# SoundChip.net
KiCad netlist of a schematic drawn in Altium Designer
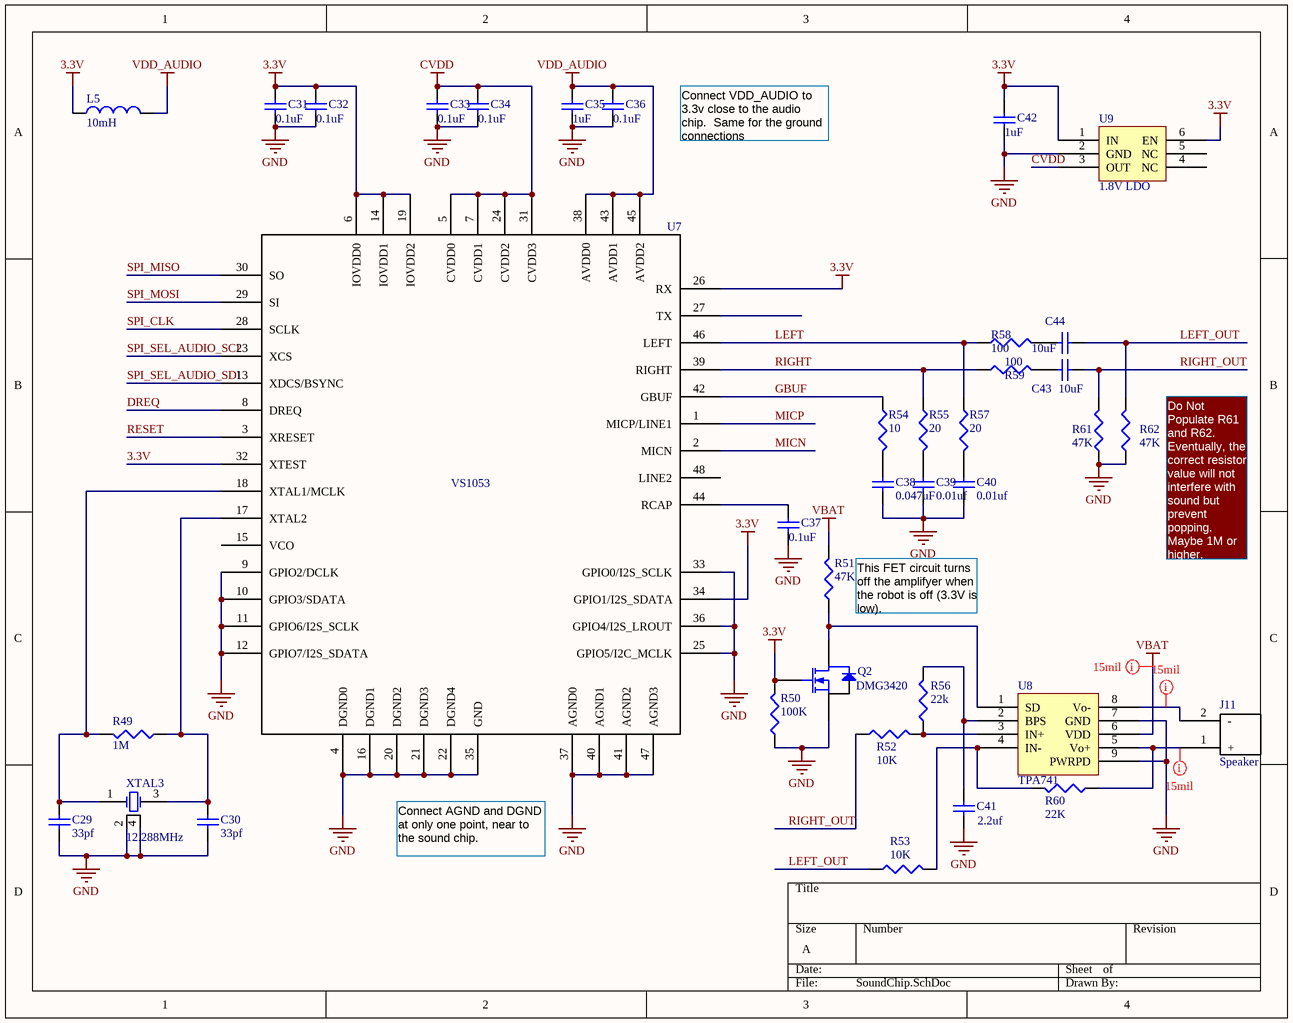
[diagram p0: SoundChip.SchDoc]

(export (version "E")
  (design (tool "Eeschema 10.0.6"))
  (components
    (comp (ref "C29")
      (value "33pf")
      (footprint "CAPC1005L")
      (description "Capacitor (Semiconductor SIM Model)")
      (fields (field (name "Comment") "Cap Semi") (field (name "PUBLISHER") "Altium Limited"))
      (libsource (lib "Miscellaneous Devices") (part "Cap Semi"))
    )
    (comp (ref "C30")
      (value "33pf")
      (footprint "CAPC1005L")
      (description "Capacitor (Semiconductor SIM Model)")
      (fields (field (name "Comment") "Cap Semi") (field (name "PUBLISHER") "Altium Limited"))
      (libsource (lib "Miscellaneous Devices") (part "Cap Semi"))
    )
    (comp (ref "C31")
      (value "0.1uF")
      (footprint "CAPC1005L")
      (description "Capacitor (Semiconductor SIM Model)")
      (fields (field (name "Comment") "Cap Semi") (field (name "PUBLISHER") "Altium Limited"))
      (libsource (lib "Miscellaneous Devices") (part "Cap Semi"))
    )
    (comp (ref "C32")
      (value "0.1uF")
      (footprint "CAPC1005L")
      (description "Capacitor (Semiconductor SIM Model)")
      (fields (field (name "Comment") "Cap Semi") (field (name "PUBLISHER") "Altium Limited"))
      (libsource (lib "Miscellaneous Devices") (part "Cap Semi"))
    )
    (comp (ref "C33")
      (value "0.1uF")
      (footprint "CAPC1005L")
      (description "Capacitor (Semiconductor SIM Model)")
      (fields (field (name "Comment") "Cap Semi") (field (name "PUBLISHER") "Altium Limited"))
      (libsource (lib "Miscellaneous Devices") (part "Cap Semi"))
    )
    (comp (ref "C34")
      (value "0.1uF")
      (footprint "CAPC1005L")
      (description "Capacitor (Semiconductor SIM Model)")
      (fields (field (name "Comment") "Cap Semi") (field (name "PUBLISHER") "Altium Limited"))
      (libsource (lib "Miscellaneous Devices") (part "Cap Semi"))
    )
    (comp (ref "C35")
      (value "1uF")
      (footprint "CAPC1608L")
      (description "Capacitor (Semiconductor SIM Model)")
      (fields (field (name "Comment") "Cap Semi") (field (name "PUBLISHER") "Altium Limited"))
      (libsource (lib "Miscellaneous Devices") (part "Cap Semi"))
    )
    (comp (ref "C36")
      (value "0.1uF")
      (footprint "CAPC1005L")
      (description "Capacitor (Semiconductor SIM Model)")
      (fields (field (name "Comment") "Cap Semi") (field (name "PUBLISHER") "Altium Limited"))
      (libsource (lib "Miscellaneous Devices") (part "Cap Semi"))
    )
    (comp (ref "C37")
      (value "0.1uF")
      (footprint "CAPC1005L")
      (description "Capacitor (Semiconductor SIM Model)")
      (fields (field (name "Comment") "Cap Semi") (field (name "PUBLISHER") "Altium Limited"))
      (libsource (lib "Miscellaneous Devices") (part "Cap Semi"))
    )
    (comp (ref "C38")
      (value "0.047uF")
      (footprint "CAPC1005L")
      (description "Capacitor (Semiconductor SIM Model)")
      (fields (field (name "Comment") "Cap Semi") (field (name "PUBLISHER") "Altium Limited"))
      (libsource (lib "Miscellaneous Devices") (part "Cap Semi"))
    )
    (comp (ref "C39")
      (value "0.01uf")
      (footprint "CAPC1005L")
      (description "Capacitor (Semiconductor SIM Model)")
      (fields (field (name "Comment") "Cap Semi") (field (name "PUBLISHER") "Altium Limited"))
      (libsource (lib "Miscellaneous Devices") (part "Cap Semi"))
    )
    (comp (ref "C40")
      (value "0.01uf")
      (footprint "CAPC1005L")
      (description "Capacitor (Semiconductor SIM Model)")
      (fields (field (name "Comment") "Cap Semi") (field (name "PUBLISHER") "Altium Limited"))
      (libsource (lib "Miscellaneous Devices") (part "Cap Semi"))
    )
    (comp (ref "C41")
      (value "2.2uf")
      (footprint "J1-0603")
      (description "Capacitor (Semiconductor SIM Model)")
      (fields (field (name "Comment") "Cap Semi") (field (name "PUBLISHER") "Altium Limited"))
      (libsource (lib "Miscellaneous Devices") (part "Cap Semi"))
    )
    (comp (ref "C42")
      (value "1uF")
      (footprint "CAPC1608L")
      (description "Capacitor (Semiconductor SIM Model)")
      (fields (field (name "Comment") "Cap Semi") (field (name "PUBLISHER") "Altium Limited"))
      (libsource (lib "Miscellaneous Devices") (part "Cap Semi"))
    )
    (comp (ref "C43")
      (value "10uF")
      (footprint "CAPC1608L")
      (description "Capacitor (Semiconductor SIM Model)")
      (fields (field (name "Comment") "Cap Semi") (field (name "PUBLISHER") "Altium Limited"))
      (libsource (lib "Miscellaneous Devices") (part "Cap Semi"))
    )
    (comp (ref "C44")
      (value "10uF")
      (footprint "CAPC1608L")
      (description "Capacitor (Semiconductor SIM Model)")
      (fields (field (name "Comment") "Cap Semi") (field (name "PUBLISHER") "Altium Limited"))
      (libsource (lib "Miscellaneous Devices") (part "Cap Semi"))
    )
    (comp (ref "J11")
      (value "Speaker")
      (footprint "BatteryConnJST")
      (libsource (lib "mrone") (part "BatteryConnJST"))
    )
    (comp (ref "L5")
      (value "10mH")
      (footprint "INDC2012L")
      (description "Inductor")
      (fields (field (name "PUBLISHER") "Altium Limited"))
      (libsource (lib "Miscellaneous Devices") (part "Inductor"))
    )
    (comp (ref "Q2")
      (value "N-Mosfet")
      (footprint "SOT-23")
      (fields (field (name "MPN") "DMG3420"))
      (libsource (lib "mrone") (part "N-Mosfet"))
    )
    (comp (ref "R49")
      (value "1M")
      (footprint "RESC1608L")
      (description "Resistor")
      (fields (field (name "Comment") "Res3") (field (name "PUBLISHER") "Altium Limited"))
      (libsource (lib "Miscellaneous Devices") (part "Res3"))
    )
    (comp (ref "R50")
      (value "100K")
      (footprint "RESC1608L")
      (description "Resistor")
      (fields (field (name "Comment") "Res3") (field (name "PUBLISHER") "Altium Limited"))
      (libsource (lib "Miscellaneous Devices") (part "Res3"))
    )
    (comp (ref "R51")
      (value "47K")
      (footprint "J1-0603")
      (description "Resistor")
      (fields (field (name "Comment") "Res3") (field (name "PUBLISHER") "Altium Limited"))
      (libsource (lib "Miscellaneous Devices") (part "Res3"))
    )
    (comp (ref "R52")
      (value "10K")
      (footprint "RESC1608L")
      (description "Resistor")
      (fields (field (name "PUBLISHER") "Altium Limited"))
      (libsource (lib "Miscellaneous Devices") (part "Res3"))
    )
    (comp (ref "R53")
      (value "10K")
      (footprint "RESC1608L")
      (description "Resistor")
      (fields (field (name "Comment") "Res3") (field (name "PUBLISHER") "Altium Limited"))
      (libsource (lib "Miscellaneous Devices") (part "Res3"))
    )
    (comp (ref "R54")
      (value "10")
      (footprint "RESC1608L")
      (description "Resistor")
      (fields (field (name "Comment") "Res3") (field (name "PUBLISHER") "Altium Limited"))
      (libsource (lib "Miscellaneous Devices") (part "Res3"))
    )
    (comp (ref "R55")
      (value "20")
      (footprint "RESC1608L")
      (description "Resistor")
      (fields (field (name "Comment") "Res3") (field (name "PUBLISHER") "Altium Limited"))
      (libsource (lib "Miscellaneous Devices") (part "Res3"))
    )
    (comp (ref "R56")
      (value "22k")
      (footprint "RESC1608L")
      (description "Resistor")
      (fields (field (name "PUBLISHER") "Altium Limited"))
      (libsource (lib "Miscellaneous Devices") (part "Res3"))
    )
    (comp (ref "R57")
      (value "20")
      (footprint "RESC1608L")
      (description "Resistor")
      (fields (field (name "Comment") "Res3") (field (name "PUBLISHER") "Altium Limited"))
      (libsource (lib "Miscellaneous Devices") (part "Res3"))
    )
    (comp (ref "R58")
      (value "100")
      (footprint "RESC1608L")
      (description "Resistor")
      (fields (field (name "Comment") "Res3") (field (name "PUBLISHER") "Altium Limited"))
      (libsource (lib "Miscellaneous Devices") (part "Res3"))
    )
    (comp (ref "R59")
      (value "100")
      (footprint "RESC1608L")
      (description "Resistor")
      (fields (field (name "Comment") "Res3") (field (name "PUBLISHER") "Altium Limited"))
      (libsource (lib "Miscellaneous Devices") (part "Res3"))
    )
    (comp (ref "R60")
      (value "22K")
      (footprint "RESC1608L")
      (description "Resistor")
      (fields (field (name "Comment") "Res3") (field (name "PUBLISHER") "Altium Limited"))
      (libsource (lib "Miscellaneous Devices") (part "Res3"))
    )
    (comp (ref "R61")
      (value "47K")
      (footprint "RESC1608L")
      (description "Resistor")
      (fields (field (name "Comment") "Res3") (field (name "PUBLISHER") "Altium Limited"))
      (libsource (lib "Miscellaneous Devices") (part "Res3"))
    )
    (comp (ref "R62")
      (value "47K")
      (footprint "RESC1608L")
      (description "Resistor")
      (fields (field (name "Comment") "Res3") (field (name "PUBLISHER") "Altium Limited"))
      (libsource (lib "Miscellaneous Devices") (part "Res3"))
    )
    (comp (ref "U7") (value "VS1053") (footprint "LQFP-48") (libsource (lib "mrone") (part "VS1053")))
    (comp (ref "U8")
      (value "TPA741")
      (footprint "audio amp")
      (libsource (lib "mrone") (part "Audio Amp TPA741"))
    )
    (comp (ref "U9") (value "1.8V LDO") (footprint "WFDFN-6") (libsource (lib "mrone") (part "1.8V_LDO")))
    (comp (ref "XTAL3") (value "12.288MHz") (footprint "CRYSTAL") (libsource (lib "mrone") (part "Crystal")))
  )
  (nets
    (net (code "1") (name "/DREQ") (class "Default")
      (node (ref "U7") (pin "8") (pinfunction "DREQ_8") (pintype "passive"))
    )
    (net (code "2") (name "/GBUF") (class "Default")
      (node (ref "R54") (pin "1") (pinfunction "1_1") (pintype "passive"))
      (node (ref "U7") (pin "42") (pinfunction "GBUF_42") (pintype "passive"))
    )
    (net (code "3") (name "/LEFT") (class "Default")
      (node (ref "R57") (pin "1") (pinfunction "1_1") (pintype "passive"))
      (node (ref "R58") (pin "1") (pinfunction "1_1") (pintype "passive"))
      (node (ref "U7") (pin "46") (pinfunction "LEFT_46") (pintype "passive"))
    )
    (net (code "4") (name "/LEFT_OUT") (class "Default")
      (node (ref "C44") (pin "1") (pinfunction "1_1") (pintype "passive"))
      (node (ref "R53") (pin "1") (pinfunction "1_1") (pintype "passive"))
      (node (ref "R62") (pin "2") (pinfunction "2_2") (pintype "passive"))
    )
    (net (code "5") (name "/MICN") (class "Default")
      (node (ref "U7") (pin "2") (pinfunction "MICN_2") (pintype "passive"))
    )
    (net (code "6") (name "/MICP") (class "Default")
      (node (ref "U7") (pin "1") (pinfunction "MICP/LINE1_1") (pintype "passive"))
    )
    (net (code "7") (name "/RESET") (class "Default")
      (node (ref "U7") (pin "3") (pinfunction "XRESET_3") (pintype "passive"))
    )
    (net (code "8") (name "/RIGHT") (class "Default")
      (node (ref "R55") (pin "1") (pinfunction "1_1") (pintype "passive"))
      (node (ref "R59") (pin "1") (pinfunction "1_1") (pintype "passive"))
      (node (ref "U7") (pin "39") (pinfunction "RIGHT_39") (pintype "passive"))
    )
    (net (code "9") (name "/RIGHT_OUT") (class "Default")
      (node (ref "C43") (pin "1") (pinfunction "1_1") (pintype "passive"))
      (node (ref "R52") (pin "1") (pinfunction "1_1") (pintype "passive"))
      (node (ref "R61") (pin "2") (pinfunction "2_2") (pintype "passive"))
    )
    (net (code "10") (name "/SPI_CLK") (class "Default")
      (node (ref "U7") (pin "28") (pinfunction "SCLK_28") (pintype "passive"))
    )
    (net (code "11") (name "/SPI_MISO") (class "Default")
      (node (ref "U7") (pin "30") (pinfunction "SO_30") (pintype "passive"))
    )
    (net (code "12") (name "/SPI_MOSI") (class "Default")
      (node (ref "U7") (pin "29") (pinfunction "SI_29") (pintype "passive"))
    )
    (net (code "13") (name "/SPI_SEL_AUDIO_SCI") (class "Default")
      (node (ref "U7") (pin "23") (pinfunction "XCS_23") (pintype "passive"))
    )
    (net (code "14") (name "/SPI_SEL_AUDIO_SDI") (class "Default")
      (node (ref "U7") (pin "13") (pinfunction "XDCS/BSYNC_13") (pintype "passive"))
    )
    (net (code "15") (name "3.3V") (class "Default")
      (node (ref "C31") (pin "2") (pinfunction "2_2") (pintype "passive"))
      (node (ref "C32") (pin "2") (pinfunction "2_2") (pintype "passive"))
      (node (ref "C42") (pin "1") (pinfunction "1_1") (pintype "passive"))
      (node (ref "L5") (pin "2") (pinfunction "2_2") (pintype "passive"))
      (node (ref "Q2") (pin "1") (pinfunction "G_1") (pintype "passive"))
      (node (ref "R50") (pin "2") (pinfunction "2_2") (pintype "passive"))
      (node (ref "U7") (pin "14") (pinfunction "IOVDD1_14") (pintype "passive"))
      (node (ref "U7") (pin "19") (pinfunction "IOVDD2_19") (pintype "passive"))
      (node (ref "U7") (pin "26") (pinfunction "RX_26") (pintype "passive"))
      (node (ref "U7") (pin "32") (pinfunction "XTEST_32") (pintype "passive"))
      (node (ref "U7") (pin "34") (pinfunction "GPIO1/I2S_SDATA_34") (pintype "passive"))
      (node (ref "U7") (pin "6") (pinfunction "IOVDD0_6") (pintype "passive"))
      (node (ref "U9") (pin "1") (pinfunction "IN_1") (pintype "passive"))
      (node (ref "U9") (pin "6") (pinfunction "EN_6") (pintype "passive"))
    )
    (net (code "16") (name "CVDD") (class "Default")
      (node (ref "C33") (pin "2") (pinfunction "2_2") (pintype "passive"))
      (node (ref "C34") (pin "2") (pinfunction "2_2") (pintype "passive"))
      (node (ref "U7") (pin "24") (pinfunction "CVDD2_24") (pintype "passive"))
      (node (ref "U7") (pin "31") (pinfunction "CVDD3_31") (pintype "passive"))
      (node (ref "U7") (pin "5") (pinfunction "CVDD0_5") (pintype "passive"))
      (node (ref "U7") (pin "7") (pinfunction "CVDD1_7") (pintype "passive"))
      (node (ref "U9") (pin "3") (pinfunction "OUT_3") (pintype "passive"))
    )
    (net (code "17") (name "GND") (class "Default")
      (node (ref "C29") (pin "2") (pinfunction "2_2") (pintype "passive"))
      (node (ref "C30") (pin "2") (pinfunction "2_2") (pintype "passive"))
      (node (ref "C31") (pin "1") (pinfunction "1_1") (pintype "passive"))
      (node (ref "C32") (pin "1") (pinfunction "1_1") (pintype "passive"))
      (node (ref "C33") (pin "1") (pinfunction "1_1") (pintype "passive"))
      (node (ref "C34") (pin "1") (pinfunction "1_1") (pintype "passive"))
      (node (ref "C35") (pin "2") (pinfunction "2_2") (pintype "passive"))
      (node (ref "C36") (pin "1") (pinfunction "1_1") (pintype "passive"))
      (node (ref "C37") (pin "1") (pinfunction "1_1") (pintype "passive"))
      (node (ref "C38") (pin "2") (pinfunction "2_2") (pintype "passive"))
      (node (ref "C39") (pin "2") (pinfunction "2_2") (pintype "passive"))
      (node (ref "C40") (pin "2") (pinfunction "2_2") (pintype "passive"))
      (node (ref "C41") (pin "1") (pinfunction "1_1") (pintype "passive"))
      (node (ref "C42") (pin "2") (pinfunction "2_2") (pintype "passive"))
      (node (ref "Q2") (pin "2") (pinfunction "S_2") (pintype "passive"))
      (node (ref "R50") (pin "1") (pinfunction "1_1") (pintype "passive"))
      (node (ref "R61") (pin "1") (pinfunction "1_1") (pintype "passive"))
      (node (ref "R62") (pin "1") (pinfunction "1_1") (pintype "passive"))
      (node (ref "U7") (pin "10") (pinfunction "GPIO3/SDATA_10") (pintype "passive"))
      (node (ref "U7") (pin "11") (pinfunction "GPIO6/I2S_SCLK_11") (pintype "passive"))
      (node (ref "U7") (pin "12") (pinfunction "GPIO7/I2S_SDATA_12") (pintype "passive"))
      (node (ref "U7") (pin "16") (pinfunction "DGND1_16") (pintype "passive"))
      (node (ref "U7") (pin "20") (pinfunction "DGND2_20") (pintype "passive"))
      (node (ref "U7") (pin "21") (pinfunction "DGND3_21") (pintype "passive"))
      (node (ref "U7") (pin "22") (pinfunction "DGND4_22") (pintype "passive"))
      (node (ref "U7") (pin "25") (pinfunction "GPIO5/I2C_MCLK_25") (pintype "passive"))
      (node (ref "U7") (pin "33") (pinfunction "GPIO0/I2S_SCLK_33") (pintype "passive"))
      (node (ref "U7") (pin "35") (pinfunction "GND_35") (pintype "passive"))
      (node (ref "U7") (pin "36") (pinfunction "GPIO4/I2S_LROUT_36") (pintype "passive"))
      (node (ref "U7") (pin "37") (pinfunction "AGND0_37") (pintype "passive"))
      (node (ref "U7") (pin "4") (pinfunction "DGND0_4") (pintype "passive"))
      (node (ref "U7") (pin "40") (pinfunction "AGND1_40") (pintype "passive"))
      (node (ref "U7") (pin "41") (pinfunction "AGND2_41") (pintype "passive"))
      (node (ref "U7") (pin "47") (pinfunction "AGND3_47") (pintype "passive"))
      (node (ref "U7") (pin "9") (pinfunction "GPIO2/DCLK_9") (pintype "passive"))
      (node (ref "U8") (pin "7") (pinfunction "GND_7") (pintype "passive"))
      (node (ref "U8") (pin "9") (pinfunction "PWRPD_9") (pintype "passive"))
      (node (ref "U9") (pin "2") (pinfunction "GND_2") (pintype "passive"))
      (node (ref "XTAL3") (pin "2") (pinfunction "GND_2") (pintype "passive"))
      (node (ref "XTAL3") (pin "4") (pinfunction "GND_4") (pintype "passive"))
    )
    (net (code "18") (name "Net-(C38-Pad1)") (class "Default")
      (node (ref "C38") (pin "1") (pinfunction "1_1") (pintype "passive"))
      (node (ref "R54") (pin "2") (pinfunction "2_2") (pintype "passive"))
    )
    (net (code "19") (name "Net-(C39-Pad1)") (class "Default")
      (node (ref "C39") (pin "1") (pinfunction "1_1") (pintype "passive"))
      (node (ref "R55") (pin "2") (pinfunction "2_2") (pintype "passive"))
    )
    (net (code "20") (name "Net-(C40-Pad1)") (class "Default")
      (node (ref "C40") (pin "1") (pinfunction "1_1") (pintype "passive"))
      (node (ref "R57") (pin "2") (pinfunction "2_2") (pintype "passive"))
    )
    (net (code "21") (name "Net-(C43-Pad2)") (class "Default")
      (node (ref "C43") (pin "2") (pinfunction "2_2") (pintype "passive"))
      (node (ref "R59") (pin "2") (pinfunction "2_2") (pintype "passive"))
    )
    (net (code "22") (name "Net-(C44-Pad2)") (class "Default")
      (node (ref "C44") (pin "2") (pinfunction "2_2") (pintype "passive"))
      (node (ref "R58") (pin "2") (pinfunction "2_2") (pintype "passive"))
    )
    (net (code "23") (name "Net-(J11-+)") (class "Default")
      (node (ref "J11") (pin "1") (pinfunction "+_1") (pintype "passive"))
      (node (ref "R60") (pin "1") (pinfunction "1_1") (pintype "passive"))
      (node (ref "U8") (pin "5") (pinfunction "Vo+_5") (pintype "passive"))
    )
    (net (code "24") (name "Net-(J11--)") (class "Default")
      (node (ref "J11") (pin "2") (pinfunction "-_2") (pintype "passive"))
      (node (ref "U8") (pin "8") (pinfunction "Vo-_8") (pintype "passive"))
    )
    (net (code "25") (name "Net-(Q2-D)") (class "Default")
      (node (ref "Q2") (pin "3") (pinfunction "D_3") (pintype "passive"))
      (node (ref "R51") (pin "1") (pinfunction "1_1") (pintype "passive"))
      (node (ref "U8") (pin "1") (pinfunction "SD_1") (pintype "passive"))
    )
    (net (code "26") (name "Net-(U7-RCAP)") (class "Default")
      (node (ref "C37") (pin "2") (pinfunction "2_2") (pintype "passive"))
      (node (ref "U7") (pin "44") (pinfunction "RCAP_44") (pintype "passive"))
    )
    (net (code "27") (name "Net-(U7-XTAL1{slash}MCLK)") (class "Default")
      (node (ref "C29") (pin "1") (pinfunction "1_1") (pintype "passive"))
      (node (ref "R49") (pin "2") (pinfunction "2_2") (pintype "passive"))
      (node (ref "U7") (pin "18") (pinfunction "XTAL1/MCLK_18") (pintype "passive"))
      (node (ref "XTAL3") (pin "1") (pinfunction "OSC1_1") (pintype "passive"))
    )
    (net (code "28") (name "Net-(U7-XTAL2)") (class "Default")
      (node (ref "C30") (pin "1") (pinfunction "1_1") (pintype "passive"))
      (node (ref "R49") (pin "1") (pinfunction "1_1") (pintype "passive"))
      (node (ref "U7") (pin "17") (pinfunction "XTAL2_17") (pintype "passive"))
      (node (ref "XTAL3") (pin "3") (pinfunction "OSC2_3") (pintype "passive"))
    )
    (net (code "29") (name "Net-(U8-BPS)") (class "Default")
      (node (ref "C41") (pin "2") (pinfunction "2_2") (pintype "passive"))
      (node (ref "R56") (pin "2") (pinfunction "2_2") (pintype "passive"))
      (node (ref "U8") (pin "2") (pinfunction "BPS_2") (pintype "passive"))
    )
    (net (code "30") (name "Net-(U8-IN+)") (class "Default")
      (node (ref "R52") (pin "2") (pinfunction "2_2") (pintype "passive"))
      (node (ref "R56") (pin "1") (pinfunction "1_1") (pintype "passive"))
      (node (ref "U8") (pin "3") (pinfunction "IN+_3") (pintype "passive"))
    )
    (net (code "31") (name "Net-(U8-IN-)") (class "Default")
      (node (ref "R53") (pin "2") (pinfunction "2_2") (pintype "passive"))
      (node (ref "R60") (pin "2") (pinfunction "2_2") (pintype "passive"))
      (node (ref "U8") (pin "4") (pinfunction "IN-_4") (pintype "passive"))
    )
    (net (code "32") (name "VBAT") (class "Default")
      (node (ref "R51") (pin "2") (pinfunction "2_2") (pintype "passive"))
      (node (ref "U8") (pin "6") (pinfunction "VDD_6") (pintype "passive"))
    )
    (net (code "33") (name "VDD_AUDIO") (class "Default")
      (node (ref "C35") (pin "1") (pinfunction "1_1") (pintype "passive"))
      (node (ref "C36") (pin "2") (pinfunction "2_2") (pintype "passive"))
      (node (ref "L5") (pin "1") (pinfunction "1_1") (pintype "passive"))
      (node (ref "U7") (pin "38") (pinfunction "AVDD0_38") (pintype "passive"))
      (node (ref "U7") (pin "43") (pinfunction "AVDD1_43") (pintype "passive"))
      (node (ref "U7") (pin "45") (pinfunction "AVDD2_45") (pintype "passive"))
    )
    (net (code "34") (name "unconnected-(U7-LINE2-Pad48)") (class "Default")
      (node (ref "U7") (pin "48") (pinfunction "LINE2_48") (pintype "passive"))
    )
    (net (code "35") (name "unconnected-(U7-TX-Pad27)") (class "Default")
      (node (ref "U7") (pin "27") (pinfunction "TX_27") (pintype "passive"))
    )
    (net (code "36") (name "unconnected-(U7-VCO-Pad15)") (class "Default")
      (node (ref "U7") (pin "15") (pinfunction "VCO_15") (pintype "passive"))
    )
    (net (code "37") (name "unconnected-(U9-NC-Pad4)") (class "Default")
      (node (ref "U9") (pin "4") (pinfunction "NC_4") (pintype "passive"))
    )
    (net (code "38") (name "unconnected-(U9-NC-Pad5)") (class "Default")
      (node (ref "U9") (pin "5") (pinfunction "NC_5") (pintype "passive"))
    )
  )
)
